# Fleet-Monitor-Ethernet-Filter.net
KiCad netlist of a schematic drawn in Altium Designer
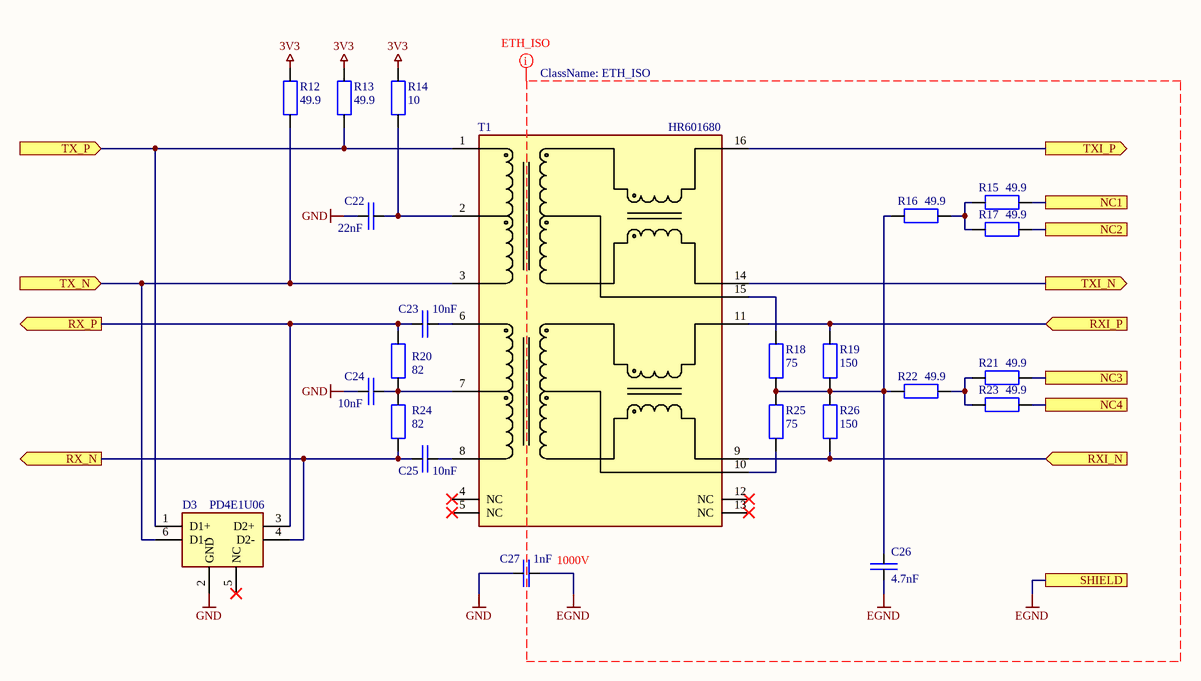
[diagram p0: Fleet-Monitor-Ethernet-Filter.SchDoc]

(export (version "E")
  (design (tool "Eeschema 10.0.6"))
  (components
    (comp (ref "C22")
      (value "22nF")
      (footprint "SMD Keramikkondensator 0603")
      (description "Multilayer Ceramic Capacitors MLCC")
      (libsource (lib "Ceramic Capacitors-E6") (part "E6 - 22nF"))
    )
    (comp (ref "C23")
      (value "10nF")
      (footprint "SMD Keramikkondensator 0603")
      (description "Multilayer Ceramic Capacitors MLCC")
      (libsource (lib "Ceramic Capacitors-E6") (part "E6 - 10nF"))
    )
    (comp (ref "C24")
      (value "10nF")
      (footprint "SMD Keramikkondensator 0603")
      (description "Multilayer Ceramic Capacitors MLCC")
      (libsource (lib "Ceramic Capacitors-E6") (part "E6 - 10nF"))
    )
    (comp (ref "C25")
      (value "10nF")
      (footprint "SMD Keramikkondensator 0603")
      (description "Multilayer Ceramic Capacitors MLCC")
      (libsource (lib "Ceramic Capacitors-E6") (part "E6 - 10nF"))
    )
    (comp (ref "C26")
      (value "4.7nF")
      (footprint "SMD Keramikkondensator 0603")
      (description "Multilayer Ceramic Capacitors MLCC")
      (libsource (lib "Fleet-Monitor") (part "E6 - 4.7nF"))
    )
    (comp (ref "C27")
      (value "1nF")
      (footprint "SMD Keramikkondensator 1808")
      (description "Multilayer Ceramic Capacitors MLCC")
      (libsource (lib "Ceramic Capacitors-E6") (part "E6 - 1nF"))
    )
    (comp (ref "D3")
      (value "PD4E1U06")
      (footprint "SMD IC SOT-363 (SC-70-6)")
      (description "ESD Suppressor")
      (libsource (lib "Fleet-Monitor") (part "PD4E1U06DCKR"))
    )
    (comp (ref "R12")
      (value "49.9")
      (footprint "SMD Widerstand 0603")
      (description "Chip Resistor")
      (libsource (lib "") (part "E96 - 49.9_1"))
    )
    (comp (ref "R13")
      (value "49.9")
      (footprint "SMD Widerstand 0603")
      (description "Chip Resistor")
      (libsource (lib "") (part "E96 - 49.9_1"))
    )
    (comp (ref "R14")
      (value "10")
      (footprint "SMD Widerstand 0603")
      (description "Chip Resistor")
      (libsource (lib "Resistors-E24") (part "E24 - 10"))
    )
    (comp (ref "R15")
      (value "49.9")
      (footprint "SMD Widerstand 0603")
      (description "Chip Resistor")
      (libsource (lib "Resistors-E96") (part "E96 - 49.9"))
    )
    (comp (ref "R16")
      (value "49.9")
      (footprint "SMD Widerstand 0603")
      (description "Chip Resistor")
      (libsource (lib "Resistors-E96") (part "E96 - 49.9"))
    )
    (comp (ref "R17")
      (value "49.9")
      (footprint "SMD Widerstand 0603")
      (description "Chip Resistor")
      (libsource (lib "Resistors-E96") (part "E96 - 49.9"))
    )
    (comp (ref "R18")
      (value "75")
      (footprint "SMD Widerstand 0603")
      (description "Chip Resistor")
      (libsource (lib "Resistors-E24") (part "E24 - 75"))
    )
    (comp (ref "R19")
      (value "150")
      (footprint "SMD Widerstand 0603")
      (description "Chip Resistor")
      (libsource (lib "Resistors-E24") (part "E24 - 150"))
    )
    (comp (ref "R20")
      (value "82")
      (footprint "SMD Widerstand 0603")
      (description "Chip Resistor")
      (libsource (lib "Resistors-E24") (part "E24 - 82"))
    )
    (comp (ref "R21")
      (value "49.9")
      (footprint "SMD Widerstand 0603")
      (description "Chip Resistor")
      (libsource (lib "Resistors-E96") (part "E96 - 49.9"))
    )
    (comp (ref "R22")
      (value "49.9")
      (footprint "SMD Widerstand 0603")
      (description "Chip Resistor")
      (libsource (lib "Resistors-E96") (part "E96 - 49.9"))
    )
    (comp (ref "R23")
      (value "49.9")
      (footprint "SMD Widerstand 0603")
      (description "Chip Resistor")
      (libsource (lib "Resistors-E96") (part "E96 - 49.9"))
    )
    (comp (ref "R24")
      (value "82")
      (footprint "SMD Widerstand 0603")
      (description "Chip Resistor")
      (libsource (lib "Resistors-E24") (part "E24 - 82"))
    )
    (comp (ref "R25")
      (value "75")
      (footprint "SMD Widerstand 0603")
      (description "Chip Resistor")
      (libsource (lib "Resistors-E24") (part "E24 - 75"))
    )
    (comp (ref "R26")
      (value "150")
      (footprint "SMD Widerstand 0603")
      (description "Chip Resistor")
      (libsource (lib "Resistors-E24") (part "E24 - 150"))
    )
    (comp (ref "T1")
      (value "HR601680")
      (footprint "SMD Transformer 500x375")
      (description "LAN 10/100 Base-T Pulse Transformer 1CT:1CT Transmitter, 1CT:1CT Receiver Surface Mount")
      (libsource (lib "Fleet-Monitor") (part "HR601680"))
    )
  )
  (nets
    (net (code "1") (name "/NC1") (class "Default")
      (node (ref "R15") (pin "1") (pinfunction "1_1") (pintype "passive"))
    )
    (net (code "2") (name "/NC2") (class "Default")
      (node (ref "R17") (pin "1") (pinfunction "1_1") (pintype "passive"))
    )
    (net (code "3") (name "/NC3") (class "Default")
      (node (ref "R21") (pin "1") (pinfunction "1_1") (pintype "passive"))
    )
    (net (code "4") (name "/NC4") (class "Default")
      (node (ref "R23") (pin "1") (pinfunction "1_1") (pintype "passive"))
    )
    (net (code "5") (name "/RXI_N") (class "Default")
      (node (ref "R26") (pin "1") (pinfunction "1_1") (pintype "passive"))
      (node (ref "T1") (pin "9") (pinfunction "RX-_9") (pintype "passive"))
    )
    (net (code "6") (name "/RXI_P") (class "Default")
      (node (ref "R19") (pin "2") (pinfunction "2_2") (pintype "passive"))
      (node (ref "T1") (pin "11") (pinfunction "RX+_11") (pintype "passive"))
    )
    (net (code "7") (name "/RX_N") (class "Default")
      (node (ref "C25") (pin "1") (pinfunction "1_1") (pintype "passive"))
      (node (ref "D3") (pin "4") (pinfunction "D2-_4") (pintype "passive"))
      (node (ref "R24") (pin "1") (pinfunction "1_1") (pintype "passive"))
    )
    (net (code "8") (name "/RX_P") (class "Default")
      (node (ref "C23") (pin "1") (pinfunction "1_1") (pintype "passive"))
      (node (ref "D3") (pin "3") (pinfunction "D2+_3") (pintype "passive"))
      (node (ref "R20") (pin "2") (pinfunction "2_2") (pintype "passive"))
    )
    (net (code "9") (name "/TXI_N") (class "Default")
      (node (ref "T1") (pin "14") (pinfunction "TX-_14") (pintype "passive"))
    )
    (net (code "10") (name "/TXI_P") (class "Default")
      (node (ref "T1") (pin "16") (pinfunction "TX+_16") (pintype "passive"))
    )
    (net (code "11") (name "/TX_N") (class "Default")
      (node (ref "D3") (pin "6") (pinfunction "D1-_6") (pintype "passive"))
      (node (ref "R12") (pin "1") (pinfunction "1_1") (pintype "passive"))
      (node (ref "T1") (pin "3") (pinfunction "TD-_3") (pintype "passive"))
    )
    (net (code "12") (name "/TX_P") (class "Default")
      (node (ref "D3") (pin "1") (pinfunction "D1+_1") (pintype "passive"))
      (node (ref "R13") (pin "1") (pinfunction "1_1") (pintype "passive"))
      (node (ref "T1") (pin "1") (pinfunction "TD+_1") (pintype "passive"))
    )
    (net (code "13") (name "3V3") (class "Default")
      (node (ref "R12") (pin "2") (pinfunction "2_2") (pintype "passive"))
      (node (ref "R13") (pin "2") (pinfunction "2_2") (pintype "passive"))
      (node (ref "R14") (pin "2") (pinfunction "2_2") (pintype "passive"))
    )
    (net (code "14") (name "EGND") (class "Default")
      (node (ref "C26") (pin "1") (pinfunction "1_1") (pintype "passive"))
      (node (ref "C27") (pin "2") (pinfunction "2_2") (pintype "passive"))
    )
    (net (code "15") (name "GND") (class "Default")
      (node (ref "C22") (pin "2") (pinfunction "2_2") (pintype "passive"))
      (node (ref "C24") (pin "2") (pinfunction "2_2") (pintype "passive"))
      (node (ref "C27") (pin "1") (pinfunction "1_1") (pintype "passive"))
      (node (ref "D3") (pin "2") (pinfunction "GND_2") (pintype "passive"))
    )
    (net (code "16") (name "Net-(C22-Pad1)") (class "Default")
      (node (ref "C22") (pin "1") (pinfunction "1_1") (pintype "passive"))
      (node (ref "R14") (pin "1") (pinfunction "1_1") (pintype "passive"))
      (node (ref "T1") (pin "2") (pinfunction "CT_2") (pintype "passive"))
    )
    (net (code "17") (name "Net-(C24-Pad1)") (class "Default")
      (node (ref "C24") (pin "1") (pinfunction "1_1") (pintype "passive"))
      (node (ref "R20") (pin "1") (pinfunction "1_1") (pintype "passive"))
      (node (ref "R24") (pin "2") (pinfunction "2_2") (pintype "passive"))
      (node (ref "T1") (pin "7") (pinfunction "CT_7") (pintype "passive"))
    )
    (net (code "18") (name "Net-(C26-Pad2)") (class "Default")
      (node (ref "C26") (pin "2") (pinfunction "2_2") (pintype "passive"))
      (node (ref "R16") (pin "2") (pinfunction "2_2") (pintype "passive"))
      (node (ref "R18") (pin "1") (pinfunction "1_1") (pintype "passive"))
      (node (ref "R19") (pin "1") (pinfunction "1_1") (pintype "passive"))
      (node (ref "R22") (pin "2") (pinfunction "2_2") (pintype "passive"))
      (node (ref "R25") (pin "2") (pinfunction "2_2") (pintype "passive"))
      (node (ref "R26") (pin "2") (pinfunction "2_2") (pintype "passive"))
    )
    (net (code "19") (name "Net-(R15-Pad2)") (class "Default")
      (node (ref "R15") (pin "2") (pinfunction "2_2") (pintype "passive"))
      (node (ref "R16") (pin "1") (pinfunction "1_1") (pintype "passive"))
      (node (ref "R17") (pin "2") (pinfunction "2_2") (pintype "passive"))
    )
    (net (code "20") (name "Net-(R18-Pad2)") (class "Default")
      (node (ref "R18") (pin "2") (pinfunction "2_2") (pintype "passive"))
      (node (ref "T1") (pin "15") (pinfunction "NC_15") (pintype "passive"))
    )
    (net (code "21") (name "Net-(R21-Pad2)") (class "Default")
      (node (ref "R21") (pin "2") (pinfunction "2_2") (pintype "passive"))
      (node (ref "R22") (pin "1") (pinfunction "1_1") (pintype "passive"))
      (node (ref "R23") (pin "2") (pinfunction "2_2") (pintype "passive"))
    )
    (net (code "22") (name "Net-(R25-Pad1)") (class "Default")
      (node (ref "R25") (pin "1") (pinfunction "1_1") (pintype "passive"))
      (node (ref "T1") (pin "10") (pinfunction "NC_10") (pintype "passive"))
    )
    (net (code "23") (name "Net-(T1-RD+)") (class "Default")
      (node (ref "C23") (pin "2") (pinfunction "2_2") (pintype "passive"))
      (node (ref "T1") (pin "6") (pinfunction "RD+_6") (pintype "passive"))
    )
    (net (code "24") (name "Net-(T1-RD-)") (class "Default")
      (node (ref "C25") (pin "2") (pinfunction "2_2") (pintype "passive"))
      (node (ref "T1") (pin "8") (pinfunction "RD-_8") (pintype "passive"))
    )
    (net (code "25") (name "unconnected-(D3-NC-Pad5)") (class "Default")
      (node (ref "D3") (pin "5") (pinfunction "NC_5") (pintype "passive+no_connect"))
    )
    (net (code "26") (name "unconnected-(T1-NC-Pad4)") (class "Default")
      (node (ref "T1") (pin "4") (pinfunction "NC_4") (pintype "passive+no_connect"))
    )
    (net (code "27") (name "unconnected-(T1-NC-Pad5)") (class "Default")
      (node (ref "T1") (pin "5") (pinfunction "NC_5") (pintype "passive+no_connect"))
    )
    (net (code "28") (name "unconnected-(T1-NC-Pad12)") (class "Default")
      (node (ref "T1") (pin "12") (pinfunction "NC_12") (pintype "passive+no_connect"))
    )
    (net (code "29") (name "unconnected-(T1-NC-Pad13)") (class "Default")
      (node (ref "T1") (pin "13") (pinfunction "NC_13") (pintype "passive+no_connect"))
    )
  )
)
